# SquidPage.net
KiCad netlist of a schematic drawn in Altium Designer
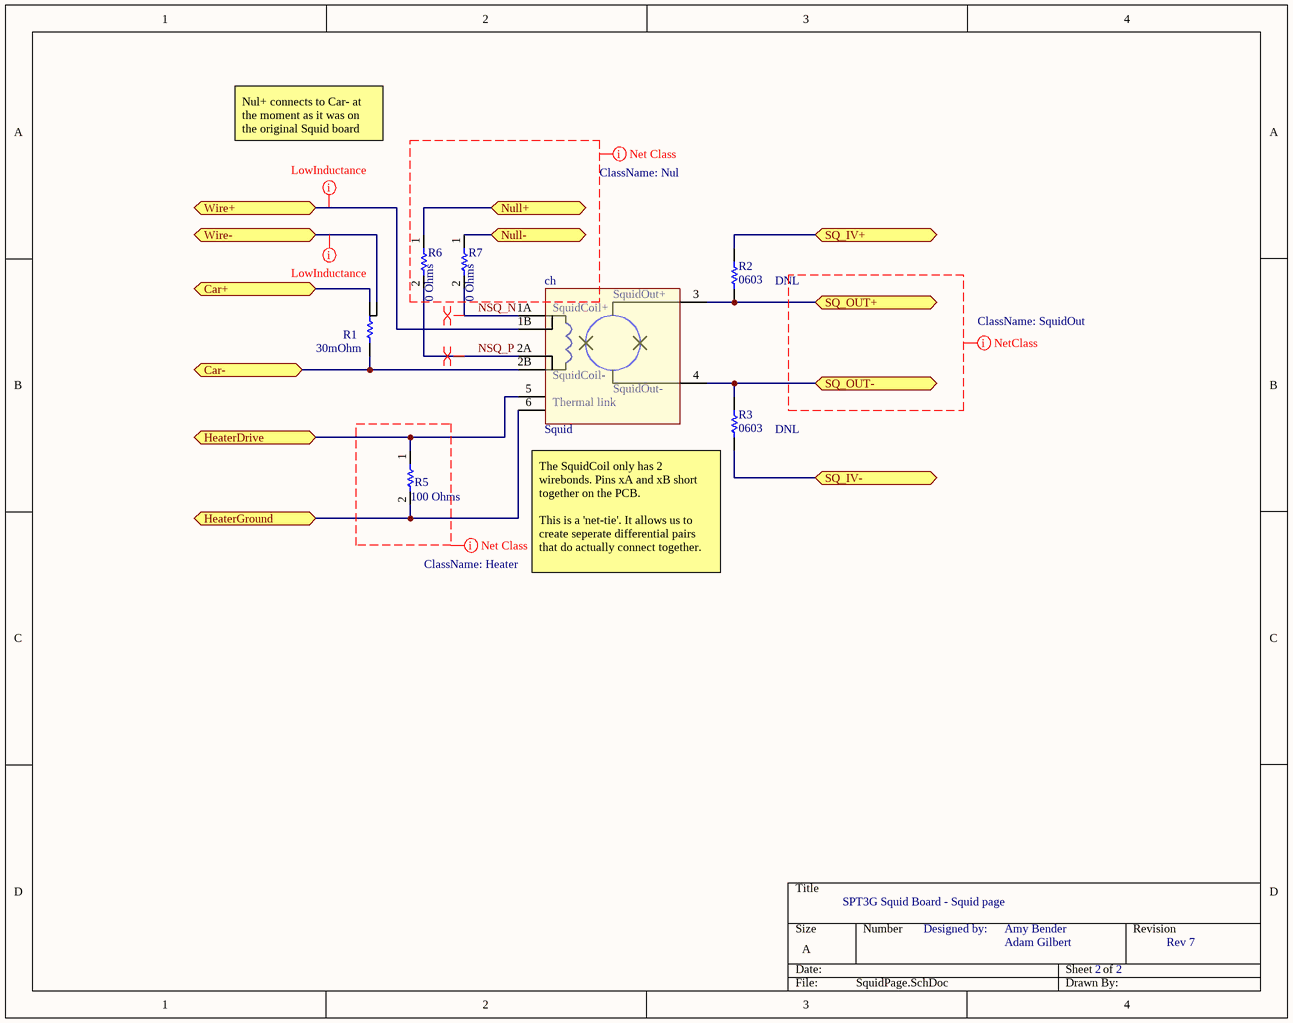
[diagram p0: SquidPage.SchDoc]

(export (version "E")
  (design (tool "Eeschema 10.0.6"))
  (components
    (comp (ref "ch") (value "Squid") (footprint "Squid2") (libsource (lib "SPT3G_LCBoard") (part "Squid")))
    (comp (ref "R1")
      (value "30mOhm")
      (footprint "0805NetTie")
      (description "Resistor")
      (fields (field (name "Comment") "ResBias"))
      (libsource (lib "SPT3G_LCBoard") (part "ResBias"))
    )
    (comp (ref "R2")
      (value "0603")
      (footprint "0603")
      (description "DNL")
      (fields (field (name "ALTIUM_VALUE") "DNL"))
      (libsource (lib "SPT3G_LCBoard") (part "Res0603"))
    )
    (comp (ref "R3")
      (value "0603")
      (footprint "0603")
      (description "DNL")
      (fields (field (name "ALTIUM_VALUE") "DNL"))
      (libsource (lib "SPT3G_LCBoard") (part "Res0603"))
    )
    (comp (ref "R5")
      (value "100 Ohms")
      (footprint "0603-NoSilk")
      (description "Resistor")
      (fields (field (name "Comment") "ResSquidBoard"))
      (libsource (lib "SPT3G_LCBoard") (part "ResSquidBoard"))
    )
    (comp (ref "R6")
      (value "0 Ohms")
      (footprint "0603")
      (description "Resistor")
      (fields (field (name "Comment") "ResSquidBoard"))
      (libsource (lib "SPT3G_LCBoard") (part "ResSquidBoard"))
    )
    (comp (ref "R7")
      (value "0 Ohms")
      (footprint "0603")
      (description "Resistor")
      (fields (field (name "Comment") "ResSquidBoard"))
      (libsource (lib "SPT3G_LCBoard") (part "ResSquidBoard"))
    )
  )
  (nets
    (net (code "1") (name "/Car+") (class "Default")
      (node (ref "R1") (pin "2A") (pinfunction "2_2A") (pintype "passive"))
    )
    (net (code "2") (name "/Car-") (class "Default")
      (node (ref "R1") (pin "1") (pinfunction "1_1") (pintype "passive"))
      (node (ref "ch") (pin "2B") (pinfunction "SquidCoil-_2B") (pintype "passive"))
    )
    (net (code "3") (name "/HeaterDrive") (class "Default")
      (node (ref "R5") (pin "1") (pinfunction "1_1") (pintype "passive"))
      (node (ref "ch") (pin "5") (pinfunction "Heater_5") (pintype "passive"))
    )
    (net (code "4") (name "/HeaterGround") (class "Default")
      (node (ref "R5") (pin "2") (pinfunction "2_2") (pintype "passive"))
      (node (ref "ch") (pin "6") (pinfunction "HeaterGnd_6") (pintype "passive"))
    )
    (net (code "5") (name "/NSQ_N") (class "Default")
      (node (ref "R7") (pin "2") (pinfunction "2_2") (pintype "passive"))
      (node (ref "ch") (pin "1A") (pinfunction "SquidCoil+_1A") (pintype "passive"))
    )
    (net (code "6") (name "/NSQ_P") (class "Default")
      (node (ref "R6") (pin "2") (pinfunction "2_2") (pintype "passive"))
      (node (ref "ch") (pin "2A") (pinfunction "SquidCoil-_2A") (pintype "passive"))
    )
    (net (code "7") (name "/Null+") (class "Default")
      (node (ref "R6") (pin "1") (pinfunction "1_1") (pintype "passive"))
    )
    (net (code "8") (name "/Null-") (class "Default")
      (node (ref "R7") (pin "1") (pinfunction "1_1") (pintype "passive"))
    )
    (net (code "9") (name "/SQ_IV+") (class "Default")
      (node (ref "R2") (pin "2") (pinfunction "2_2") (pintype "passive"))
    )
    (net (code "10") (name "/SQ_IV-") (class "Default")
      (node (ref "R3") (pin "1") (pinfunction "1_1") (pintype "passive"))
    )
    (net (code "11") (name "/SQ_OUT+") (class "Default")
      (node (ref "R2") (pin "1") (pinfunction "1_1") (pintype "passive"))
      (node (ref "ch") (pin "3") (pinfunction "SQUID+_3") (pintype "passive"))
    )
    (net (code "12") (name "/SQ_OUT-") (class "Default")
      (node (ref "R3") (pin "2") (pinfunction "2_2") (pintype "passive"))
      (node (ref "ch") (pin "4") (pinfunction "SQUID-_4") (pintype "passive"))
    )
    (net (code "13") (name "/Wire+") (class "Default")
      (node (ref "ch") (pin "1B") (pinfunction "SquidCoil+_1B") (pintype "passive"))
    )
    (net (code "14") (name "/Wire-") (class "Default")
      (node (ref "R1") (pin "2B") (pinfunction "2_2B") (pintype "passive"))
    )
  )
)
